# MATRIX-x1.net
KiCad netlist of a schematic drawn in Altium Designer
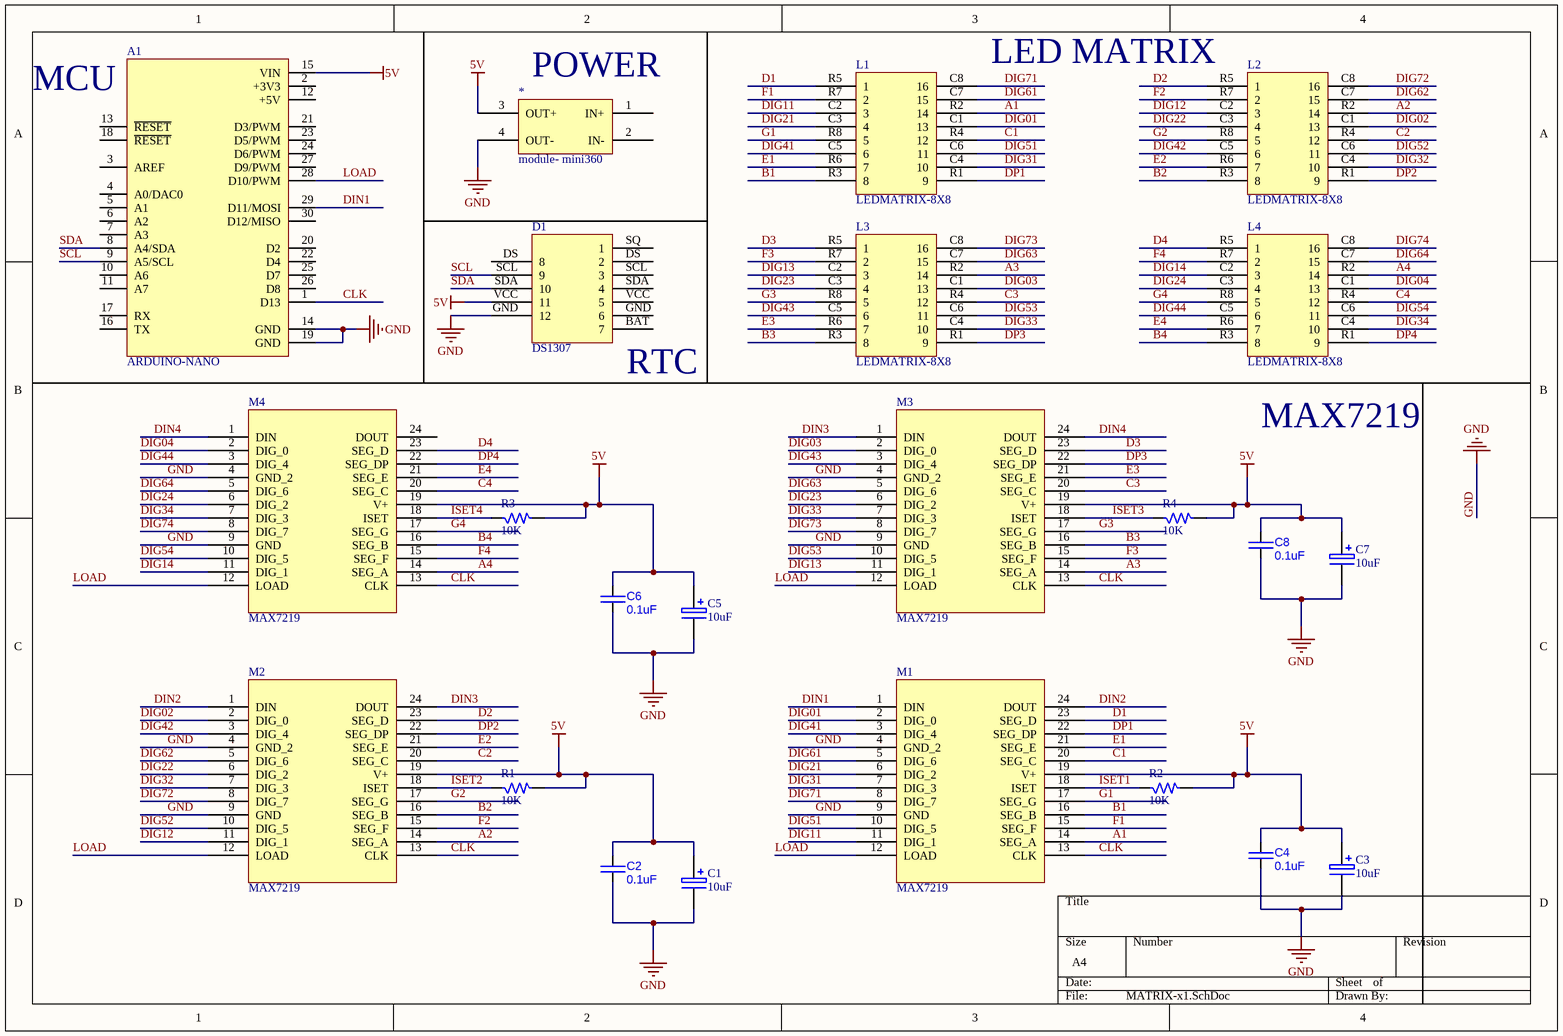
[diagram p0: MATRIX-x1.SchDoc]

(export (version "E")
  (design (tool "Eeschema 10.0.6"))
  (components
    (comp (ref "*")
      (value "module- mini360")
      (footprint "MODULE-MINI360")
      (libsource (lib "KHOEMACH_LIB") (part "module- mini360"))
    )
    (comp (ref "A1")
      (value "ARDUINO-NANO")
      (footprint "ARDUINO-NANO")
      (libsource (lib "KHOEMACH_LIB") (part "ARDUINO-NANO"))
    )
    (comp (ref "C1")
      (value "10uF")
      (footprint "CP1/2")
      (description "Cap")
      (libsource (lib "My library altium") (part "CAP hoa"))
    )
    (comp (ref "C2")
      (value "0.1uF")
      (footprint "CAPC2012X135N")
      (description "Capacitor SMD Cer 1.8nF 10% 50V X7R 0805")
      (fields (field (name "TOLERANCE") "±10%") (field (name "Comment") "approved sub OK"))
      (libsource (lib "My library altium") (part "CAP C_0805"))
    )
    (comp (ref "C3")
      (value "10uF")
      (footprint "CP1/2")
      (description "Cap")
      (libsource (lib "My library altium") (part "CAP hoa"))
    )
    (comp (ref "C4")
      (value "0.1uF")
      (footprint "CAPC2012X135N")
      (description "Capacitor SMD Cer 1.8nF 10% 50V X7R 0805")
      (fields (field (name "TOLERANCE") "±10%") (field (name "Comment") "approved sub OK"))
      (libsource (lib "My library altium") (part "CAP C_0805"))
    )
    (comp (ref "C5")
      (value "10uF")
      (footprint "CP1/2")
      (description "Cap")
      (libsource (lib "My library altium") (part "CAP hoa"))
    )
    (comp (ref "C6")
      (value "0.1uF")
      (footprint "CAPC2012X135N")
      (description "Capacitor SMD Cer 1.8nF 10% 50V X7R 0805")
      (fields (field (name "TOLERANCE") "±10%") (field (name "Comment") "approved sub OK"))
      (libsource (lib "My library altium") (part "CAP C_0805"))
    )
    (comp (ref "C7")
      (value "10uF")
      (footprint "CP1/2")
      (description "Cap")
      (libsource (lib "My library altium") (part "CAP hoa"))
    )
    (comp (ref "C8")
      (value "0.1uF")
      (footprint "CAPC2012X135N")
      (description "Capacitor SMD Cer 1.8nF 10% 50V X7R 0805")
      (fields (field (name "TOLERANCE") "±10%") (field (name "Comment") "approved sub OK"))
      (libsource (lib "My library altium") (part "CAP C_0805"))
    )
    (comp (ref "D1")
      (value "DS1307")
      (footprint "DS1307-MODULE")
      (libsource (lib "KHOEMACH_LIB") (part "DS1307_MODULE"))
    )
    (comp (ref "L1")
      (value "LEDMATRIX-8X8")
      (footprint "LEDMATRIX_8X8")
      (libsource (lib "KHOEMACH_LIB") (part "LEDMATRIX-8X8"))
    )
    (comp (ref "L2")
      (value "LEDMATRIX-8X8")
      (footprint "LEDMATRIX_8X8")
      (libsource (lib "KHOEMACH_LIB") (part "LEDMATRIX-8X8"))
    )
    (comp (ref "L3")
      (value "LEDMATRIX-8X8")
      (footprint "LEDMATRIX_8X8")
      (libsource (lib "KHOEMACH_LIB") (part "LEDMATRIX-8X8"))
    )
    (comp (ref "L4")
      (value "LEDMATRIX-8X8")
      (footprint "LEDMATRIX_8X8")
      (libsource (lib "KHOEMACH_LIB") (part "LEDMATRIX-8X8"))
    )
    (comp (ref "M1")
      (value "MAX7219")
      (footprint "MAX7219")
      (libsource (lib "KHOEMACH_LIB") (part "MAX7219"))
    )
    (comp (ref "M2")
      (value "MAX7219")
      (footprint "MAX7219")
      (libsource (lib "KHOEMACH_LIB") (part "MAX7219"))
    )
    (comp (ref "M3")
      (value "MAX7219")
      (footprint "MAX7219")
      (libsource (lib "KHOEMACH_LIB") (part "MAX7219"))
    )
    (comp (ref "M4")
      (value "MAX7219")
      (footprint "MAX7219")
      (libsource (lib "KHOEMACH_LIB") (part "MAX7219"))
    )
    (comp (ref "R1")
      (value "10K")
      (footprint "SM-RES-1206")
      (description "Resistor 1/4W")
      (libsource (lib "syhaunguyen") (part "R"))
    )
    (comp (ref "R2")
      (value "10K")
      (footprint "SM-RES-1206")
      (description "Resistor 1/4W")
      (libsource (lib "syhaunguyen") (part "R"))
    )
    (comp (ref "R3")
      (value "10K")
      (footprint "SM-RES-1206")
      (description "Resistor 1/4W")
      (libsource (lib "syhaunguyen") (part "R"))
    )
    (comp (ref "R4")
      (value "10K")
      (footprint "SM-RES-1206")
      (description "Resistor 1/4W")
      (libsource (lib "syhaunguyen") (part "R"))
    )
  )
  (nets
    (net (code "1") (name "/A1") (class "Default")
      (node (ref "L1") (pin "R2") (pinfunction "14_R2") (pintype "passive"))
      (node (ref "M1") (pin "14") (pinfunction "SEG_A_14") (pintype "passive"))
    )
    (net (code "2") (name "/A2") (class "Default")
      (node (ref "L2") (pin "R2") (pinfunction "14_R2") (pintype "passive"))
      (node (ref "M2") (pin "14") (pinfunction "SEG_A_14") (pintype "passive"))
    )
    (net (code "3") (name "/A3") (class "Default")
      (node (ref "L3") (pin "R2") (pinfunction "14_R2") (pintype "passive"))
      (node (ref "M3") (pin "14") (pinfunction "SEG_A_14") (pintype "passive"))
    )
    (net (code "4") (name "/A4") (class "Default")
      (node (ref "L4") (pin "R2") (pinfunction "14_R2") (pintype "passive"))
      (node (ref "M4") (pin "14") (pinfunction "SEG_A_14") (pintype "passive"))
    )
    (net (code "5") (name "/B1") (class "Default")
      (node (ref "L1") (pin "R3") (pinfunction "8_R3") (pintype "passive"))
      (node (ref "M1") (pin "16") (pinfunction "SEG_B_16") (pintype "passive"))
    )
    (net (code "6") (name "/B2") (class "Default")
      (node (ref "L2") (pin "R3") (pinfunction "8_R3") (pintype "passive"))
      (node (ref "M2") (pin "16") (pinfunction "SEG_B_16") (pintype "passive"))
    )
    (net (code "7") (name "/B3") (class "Default")
      (node (ref "L3") (pin "R3") (pinfunction "8_R3") (pintype "passive"))
      (node (ref "M3") (pin "16") (pinfunction "SEG_B_16") (pintype "passive"))
    )
    (net (code "8") (name "/B4") (class "Default")
      (node (ref "L4") (pin "R3") (pinfunction "8_R3") (pintype "passive"))
      (node (ref "M4") (pin "16") (pinfunction "SEG_B_16") (pintype "passive"))
    )
    (net (code "9") (name "/C1") (class "Default")
      (node (ref "L1") (pin "R4") (pinfunction "12_R4") (pintype "passive"))
      (node (ref "M1") (pin "20") (pinfunction "SEG_C_20") (pintype "passive"))
    )
    (net (code "10") (name "/C2") (class "Default")
      (node (ref "L2") (pin "R4") (pinfunction "12_R4") (pintype "passive"))
      (node (ref "M2") (pin "20") (pinfunction "SEG_C_20") (pintype "passive"))
    )
    (net (code "11") (name "/C3") (class "Default")
      (node (ref "L3") (pin "R4") (pinfunction "12_R4") (pintype "passive"))
      (node (ref "M3") (pin "20") (pinfunction "SEG_C_20") (pintype "passive"))
    )
    (net (code "12") (name "/C4") (class "Default")
      (node (ref "L4") (pin "R4") (pinfunction "12_R4") (pintype "passive"))
      (node (ref "M4") (pin "20") (pinfunction "SEG_C_20") (pintype "passive"))
    )
    (net (code "13") (name "/CLK") (class "Default")
      (node (ref "A1") (pin "1") (pinfunction "D13_1") (pintype "passive"))
      (node (ref "M1") (pin "13") (pinfunction "CLK_13") (pintype "passive"))
      (node (ref "M2") (pin "13") (pinfunction "CLK_13") (pintype "passive"))
      (node (ref "M3") (pin "13") (pinfunction "CLK_13") (pintype "passive"))
      (node (ref "M4") (pin "13") (pinfunction "CLK_13") (pintype "passive"))
    )
    (net (code "14") (name "/D1") (class "Default")
      (node (ref "L1") (pin "R5") (pinfunction "1_R5") (pintype "passive"))
      (node (ref "M1") (pin "23") (pinfunction "SEG_D_23") (pintype "passive"))
    )
    (net (code "15") (name "/D2") (class "Default")
      (node (ref "L2") (pin "R5") (pinfunction "1_R5") (pintype "passive"))
      (node (ref "M2") (pin "23") (pinfunction "SEG_D_23") (pintype "passive"))
    )
    (net (code "16") (name "/D3") (class "Default")
      (node (ref "L3") (pin "R5") (pinfunction "1_R5") (pintype "passive"))
      (node (ref "M3") (pin "23") (pinfunction "SEG_D_23") (pintype "passive"))
    )
    (net (code "17") (name "/D4") (class "Default")
      (node (ref "L4") (pin "R5") (pinfunction "1_R5") (pintype "passive"))
      (node (ref "M4") (pin "23") (pinfunction "SEG_D_23") (pintype "passive"))
    )
    (net (code "18") (name "/DIG01") (class "Default")
      (node (ref "L1") (pin "C1") (pinfunction "13_C1") (pintype "passive"))
      (node (ref "M1") (pin "2") (pinfunction "DIG_0_2") (pintype "passive"))
    )
    (net (code "19") (name "/DIG02") (class "Default")
      (node (ref "L2") (pin "C1") (pinfunction "13_C1") (pintype "passive"))
      (node (ref "M2") (pin "2") (pinfunction "DIG_0_2") (pintype "passive"))
    )
    (net (code "20") (name "/DIG03") (class "Default")
      (node (ref "L3") (pin "C1") (pinfunction "13_C1") (pintype "passive"))
      (node (ref "M3") (pin "2") (pinfunction "DIG_0_2") (pintype "passive"))
    )
    (net (code "21") (name "/DIG04") (class "Default")
      (node (ref "L4") (pin "C1") (pinfunction "13_C1") (pintype "passive"))
      (node (ref "M4") (pin "2") (pinfunction "DIG_0_2") (pintype "passive"))
    )
    (net (code "22") (name "/DIG11") (class "Default")
      (node (ref "L1") (pin "C2") (pinfunction "3_C2") (pintype "passive"))
      (node (ref "M1") (pin "11") (pinfunction "DIG_1_11") (pintype "passive"))
    )
    (net (code "23") (name "/DIG12") (class "Default")
      (node (ref "L2") (pin "C2") (pinfunction "3_C2") (pintype "passive"))
      (node (ref "M2") (pin "11") (pinfunction "DIG_1_11") (pintype "passive"))
    )
    (net (code "24") (name "/DIG13") (class "Default")
      (node (ref "L3") (pin "C2") (pinfunction "3_C2") (pintype "passive"))
      (node (ref "M3") (pin "11") (pinfunction "DIG_1_11") (pintype "passive"))
    )
    (net (code "25") (name "/DIG14") (class "Default")
      (node (ref "L4") (pin "C2") (pinfunction "3_C2") (pintype "passive"))
      (node (ref "M4") (pin "11") (pinfunction "DIG_1_11") (pintype "passive"))
    )
    (net (code "26") (name "/DIG21") (class "Default")
      (node (ref "L1") (pin "C3") (pinfunction "4_C3") (pintype "passive"))
      (node (ref "M1") (pin "6") (pinfunction "DIG_2_6") (pintype "passive"))
    )
    (net (code "27") (name "/DIG22") (class "Default")
      (node (ref "L2") (pin "C3") (pinfunction "4_C3") (pintype "passive"))
      (node (ref "M2") (pin "6") (pinfunction "DIG_2_6") (pintype "passive"))
    )
    (net (code "28") (name "/DIG23") (class "Default")
      (node (ref "L3") (pin "C3") (pinfunction "4_C3") (pintype "passive"))
      (node (ref "M3") (pin "6") (pinfunction "DIG_2_6") (pintype "passive"))
    )
    (net (code "29") (name "/DIG24") (class "Default")
      (node (ref "L4") (pin "C3") (pinfunction "4_C3") (pintype "passive"))
      (node (ref "M4") (pin "6") (pinfunction "DIG_2_6") (pintype "passive"))
    )
    (net (code "30") (name "/DIG31") (class "Default")
      (node (ref "L1") (pin "C4") (pinfunction "10_C4") (pintype "passive"))
      (node (ref "M1") (pin "7") (pinfunction "DIG_3_7") (pintype "passive"))
    )
    (net (code "31") (name "/DIG32") (class "Default")
      (node (ref "L2") (pin "C4") (pinfunction "10_C4") (pintype "passive"))
      (node (ref "M2") (pin "7") (pinfunction "DIG_3_7") (pintype "passive"))
    )
    (net (code "32") (name "/DIG33") (class "Default")
      (node (ref "L3") (pin "C4") (pinfunction "10_C4") (pintype "passive"))
      (node (ref "M3") (pin "7") (pinfunction "DIG_3_7") (pintype "passive"))
    )
    (net (code "33") (name "/DIG34") (class "Default")
      (node (ref "L4") (pin "C4") (pinfunction "10_C4") (pintype "passive"))
      (node (ref "M4") (pin "7") (pinfunction "DIG_3_7") (pintype "passive"))
    )
    (net (code "34") (name "/DIG41") (class "Default")
      (node (ref "L1") (pin "C5") (pinfunction "6_C5") (pintype "passive"))
      (node (ref "M1") (pin "3") (pinfunction "DIG_4_3") (pintype "passive"))
    )
    (net (code "35") (name "/DIG42") (class "Default")
      (node (ref "L2") (pin "C5") (pinfunction "6_C5") (pintype "passive"))
      (node (ref "M2") (pin "3") (pinfunction "DIG_4_3") (pintype "passive"))
    )
    (net (code "36") (name "/DIG43") (class "Default")
      (node (ref "L3") (pin "C5") (pinfunction "6_C5") (pintype "passive"))
      (node (ref "M3") (pin "3") (pinfunction "DIG_4_3") (pintype "passive"))
    )
    (net (code "37") (name "/DIG44") (class "Default")
      (node (ref "L4") (pin "C5") (pinfunction "6_C5") (pintype "passive"))
      (node (ref "M4") (pin "3") (pinfunction "DIG_4_3") (pintype "passive"))
    )
    (net (code "38") (name "/DIG51") (class "Default")
      (node (ref "L1") (pin "C6") (pinfunction "11_C6") (pintype "passive"))
      (node (ref "M1") (pin "10") (pinfunction "DIG_5_10") (pintype "passive"))
    )
    (net (code "39") (name "/DIG52") (class "Default")
      (node (ref "L2") (pin "C6") (pinfunction "11_C6") (pintype "passive"))
      (node (ref "M2") (pin "10") (pinfunction "DIG_5_10") (pintype "passive"))
    )
    (net (code "40") (name "/DIG53") (class "Default")
      (node (ref "L3") (pin "C6") (pinfunction "11_C6") (pintype "passive"))
      (node (ref "M3") (pin "10") (pinfunction "DIG_5_10") (pintype "passive"))
    )
    (net (code "41") (name "/DIG54") (class "Default")
      (node (ref "L4") (pin "C6") (pinfunction "11_C6") (pintype "passive"))
      (node (ref "M4") (pin "10") (pinfunction "DIG_5_10") (pintype "passive"))
    )
    (net (code "42") (name "/DIG61") (class "Default")
      (node (ref "L1") (pin "C7") (pinfunction "15_C7") (pintype "passive"))
      (node (ref "M1") (pin "5") (pinfunction "DIG_6_5") (pintype "passive"))
    )
    (net (code "43") (name "/DIG62") (class "Default")
      (node (ref "L2") (pin "C7") (pinfunction "15_C7") (pintype "passive"))
      (node (ref "M2") (pin "5") (pinfunction "DIG_6_5") (pintype "passive"))
    )
    (net (code "44") (name "/DIG63") (class "Default")
      (node (ref "L3") (pin "C7") (pinfunction "15_C7") (pintype "passive"))
      (node (ref "M3") (pin "5") (pinfunction "DIG_6_5") (pintype "passive"))
    )
    (net (code "45") (name "/DIG64") (class "Default")
      (node (ref "L4") (pin "C7") (pinfunction "15_C7") (pintype "passive"))
      (node (ref "M4") (pin "5") (pinfunction "DIG_6_5") (pintype "passive"))
    )
    (net (code "46") (name "/DIG71") (class "Default")
      (node (ref "L1") (pin "C8") (pinfunction "16_C8") (pintype "passive"))
      (node (ref "M1") (pin "8") (pinfunction "DIG_7_8") (pintype "passive"))
    )
    (net (code "47") (name "/DIG72") (class "Default")
      (node (ref "L2") (pin "C8") (pinfunction "16_C8") (pintype "passive"))
      (node (ref "M2") (pin "8") (pinfunction "DIG_7_8") (pintype "passive"))
    )
    (net (code "48") (name "/DIG73") (class "Default")
      (node (ref "L3") (pin "C8") (pinfunction "16_C8") (pintype "passive"))
      (node (ref "M3") (pin "8") (pinfunction "DIG_7_8") (pintype "passive"))
    )
    (net (code "49") (name "/DIG74") (class "Default")
      (node (ref "L4") (pin "C8") (pinfunction "16_C8") (pintype "passive"))
      (node (ref "M4") (pin "8") (pinfunction "DIG_7_8") (pintype "passive"))
    )
    (net (code "50") (name "/DIN1") (class "Default")
      (node (ref "A1") (pin "29") (pinfunction "D11/MOSI_29") (pintype "passive"))
      (node (ref "M1") (pin "1") (pinfunction "DIN_1") (pintype "passive"))
    )
    (net (code "51") (name "/DIN2") (class "Default")
      (node (ref "M1") (pin "24") (pinfunction "DOUT_24") (pintype "passive"))
      (node (ref "M2") (pin "1") (pinfunction "DIN_1") (pintype "passive"))
    )
    (net (code "52") (name "/DIN3") (class "Default")
      (node (ref "M2") (pin "24") (pinfunction "DOUT_24") (pintype "passive"))
      (node (ref "M3") (pin "1") (pinfunction "DIN_1") (pintype "passive"))
    )
    (net (code "53") (name "/DIN4") (class "Default")
      (node (ref "M3") (pin "24") (pinfunction "DOUT_24") (pintype "passive"))
      (node (ref "M4") (pin "1") (pinfunction "DIN_1") (pintype "passive"))
    )
    (net (code "54") (name "/DP1") (class "Default")
      (node (ref "L1") (pin "R1") (pinfunction "9_R1") (pintype "passive"))
      (node (ref "M1") (pin "22") (pinfunction "SEG_DP_22") (pintype "passive"))
    )
    (net (code "55") (name "/DP2") (class "Default")
      (node (ref "L2") (pin "R1") (pinfunction "9_R1") (pintype "passive"))
      (node (ref "M2") (pin "22") (pinfunction "SEG_DP_22") (pintype "passive"))
    )
    (net (code "56") (name "/DP3") (class "Default")
      (node (ref "L3") (pin "R1") (pinfunction "9_R1") (pintype "passive"))
      (node (ref "M3") (pin "22") (pinfunction "SEG_DP_22") (pintype "passive"))
    )
    (net (code "57") (name "/DP4") (class "Default")
      (node (ref "L4") (pin "R1") (pinfunction "9_R1") (pintype "passive"))
      (node (ref "M4") (pin "22") (pinfunction "SEG_DP_22") (pintype "passive"))
    )
    (net (code "58") (name "/E1") (class "Default")
      (node (ref "L1") (pin "R6") (pinfunction "7_R6") (pintype "passive"))
      (node (ref "M1") (pin "21") (pinfunction "SEG_E_21") (pintype "passive"))
    )
    (net (code "59") (name "/E2") (class "Default")
      (node (ref "L2") (pin "R6") (pinfunction "7_R6") (pintype "passive"))
      (node (ref "M2") (pin "21") (pinfunction "SEG_E_21") (pintype "passive"))
    )
    (net (code "60") (name "/E3") (class "Default")
      (node (ref "L3") (pin "R6") (pinfunction "7_R6") (pintype "passive"))
      (node (ref "M3") (pin "21") (pinfunction "SEG_E_21") (pintype "passive"))
    )
    (net (code "61") (name "/E4") (class "Default")
      (node (ref "L4") (pin "R6") (pinfunction "7_R6") (pintype "passive"))
      (node (ref "M4") (pin "21") (pinfunction "SEG_E_21") (pintype "passive"))
    )
    (net (code "62") (name "/F1") (class "Default")
      (node (ref "L1") (pin "R7") (pinfunction "2_R7") (pintype "passive"))
      (node (ref "M1") (pin "15") (pinfunction "SEG_F_15") (pintype "passive"))
    )
    (net (code "63") (name "/F2") (class "Default")
      (node (ref "L2") (pin "R7") (pinfunction "2_R7") (pintype "passive"))
      (node (ref "M2") (pin "15") (pinfunction "SEG_F_15") (pintype "passive"))
    )
    (net (code "64") (name "/F3") (class "Default")
      (node (ref "L3") (pin "R7") (pinfunction "2_R7") (pintype "passive"))
      (node (ref "M3") (pin "15") (pinfunction "SEG_F_15") (pintype "passive"))
    )
    (net (code "65") (name "/F4") (class "Default")
      (node (ref "L4") (pin "R7") (pinfunction "2_R7") (pintype "passive"))
      (node (ref "M4") (pin "15") (pinfunction "SEG_F_15") (pintype "passive"))
    )
    (net (code "66") (name "/G1") (class "Default")
      (node (ref "L1") (pin "R8") (pinfunction "5_R8") (pintype "passive"))
      (node (ref "M1") (pin "17") (pinfunction "SEG_G_17") (pintype "passive"))
    )
    (net (code "67") (name "/G2") (class "Default")
      (node (ref "L2") (pin "R8") (pinfunction "5_R8") (pintype "passive"))
      (node (ref "M2") (pin "17") (pinfunction "SEG_G_17") (pintype "passive"))
    )
    (net (code "68") (name "/G3") (class "Default")
      (node (ref "L3") (pin "R8") (pinfunction "5_R8") (pintype "passive"))
      (node (ref "M3") (pin "17") (pinfunction "SEG_G_17") (pintype "passive"))
    )
    (net (code "69") (name "/G4") (class "Default")
      (node (ref "L4") (pin "R8") (pinfunction "5_R8") (pintype "passive"))
      (node (ref "M4") (pin "17") (pinfunction "SEG_G_17") (pintype "passive"))
    )
    (net (code "70") (name "/ISET1") (class "Default")
      (node (ref "M1") (pin "18") (pinfunction "ISET_18") (pintype "passive"))
      (node (ref "R2") (pin "1") (pinfunction "1_1") (pintype "passive"))
    )
    (net (code "71") (name "/ISET2") (class "Default")
      (node (ref "M2") (pin "18") (pinfunction "ISET_18") (pintype "passive"))
      (node (ref "R1") (pin "1") (pinfunction "1_1") (pintype "passive"))
    )
    (net (code "72") (name "/ISET3") (class "Default")
      (node (ref "M3") (pin "18") (pinfunction "ISET_18") (pintype "passive"))
      (node (ref "R4") (pin "1") (pinfunction "1_1") (pintype "passive"))
    )
    (net (code "73") (name "/ISET4") (class "Default")
      (node (ref "M4") (pin "18") (pinfunction "ISET_18") (pintype "passive"))
      (node (ref "R3") (pin "1") (pinfunction "1_1") (pintype "passive"))
    )
    (net (code "74") (name "/LOAD") (class "Default")
      (node (ref "A1") (pin "28") (pinfunction "D10/PWM_28") (pintype "passive"))
      (node (ref "M1") (pin "12") (pinfunction "LOAD_12") (pintype "passive"))
      (node (ref "M2") (pin "12") (pinfunction "LOAD_12") (pintype "passive"))
      (node (ref "M3") (pin "12") (pinfunction "LOAD_12") (pintype "passive"))
      (node (ref "M4") (pin "12") (pinfunction "LOAD_12") (pintype "passive"))
    )
    (net (code "75") (name "/SCL") (class "Default")
      (node (ref "A1") (pin "9") (pinfunction "A5/SCL_9") (pintype "passive"))
      (node (ref "D1") (pin "SCL") (pinfunction "9_SCL") (pintype "passive"))
    )
    (net (code "76") (name "/SDA") (class "Default")
      (node (ref "A1") (pin "8") (pinfunction "A4/SDA_8") (pintype "passive"))
      (node (ref "D1") (pin "SDA") (pinfunction "10_SDA") (pintype "passive"))
    )
    (net (code "77") (name "5V") (class "Default")
      (node (ref "*") (pin "3") (pinfunction "OUT+_3") (pintype "passive"))
      (node (ref "A1") (pin "15") (pinfunction "VIN_15") (pintype "passive"))
      (node (ref "C1") (pin "1") (pintype "passive"))
      (node (ref "C2") (pin "1") (pintype "passive"))
      (node (ref "C3") (pin "1") (pintype "passive"))
      (node (ref "C4") (pin "1") (pintype "passive"))
      (node (ref "C5") (pin "1") (pintype "passive"))
      (node (ref "C6") (pin "1") (pintype "passive"))
      (node (ref "C7") (pin "1") (pintype "passive"))
      (node (ref "C8") (pin "1") (pintype "passive"))
      (node (ref "D1") (pin "VCC") (pinfunction "11_VCC") (pintype "passive"))
      (node (ref "M1") (pin "19") (pinfunction "V+_19") (pintype "power_in"))
      (node (ref "M2") (pin "19") (pinfunction "V+_19") (pintype "power_in"))
      (node (ref "M3") (pin "19") (pinfunction "V+_19") (pintype "power_in"))
      (node (ref "M4") (pin "19") (pinfunction "V+_19") (pintype "power_in"))
      (node (ref "R1") (pin "2") (pinfunction "2_2") (pintype "passive"))
      (node (ref "R2") (pin "2") (pinfunction "2_2") (pintype "passive"))
      (node (ref "R3") (pin "2") (pinfunction "2_2") (pintype "passive"))
      (node (ref "R4") (pin "2") (pinfunction "2_2") (pintype "passive"))
    )
    (net (code "78") (name "GND") (class "Default")
      (node (ref "*") (pin "4") (pinfunction "OUT-_4") (pintype "passive"))
      (node (ref "A1") (pin "14") (pinfunction "GND_14") (pintype "passive"))
      (node (ref "A1") (pin "19") (pinfunction "GND_19") (pintype "passive"))
      (node (ref "C1") (pin "2") (pintype "passive"))
      (node (ref "C2") (pin "2") (pintype "passive"))
      (node (ref "C3") (pin "2") (pintype "passive"))
      (node (ref "C4") (pin "2") (pintype "passive"))
      (node (ref "C5") (pin "2") (pintype "passive"))
      (node (ref "C6") (pin "2") (pintype "passive"))
      (node (ref "C7") (pin "2") (pintype "passive"))
      (node (ref "C8") (pin "2") (pintype "passive"))
      (node (ref "D1") (pin "GND") (pinfunction "12_GND") (pintype "passive"))
      (node (ref "M1") (pin "4") (pinfunction "GND_2_4") (pintype "power_in"))
      (node (ref "M1") (pin "9") (pinfunction "GND_9") (pintype "power_in"))
      (node (ref "M2") (pin "4") (pinfunction "GND_2_4") (pintype "power_in"))
      (node (ref "M2") (pin "9") (pinfunction "GND_9") (pintype "power_in"))
      (node (ref "M3") (pin "4") (pinfunction "GND_2_4") (pintype "power_in"))
      (node (ref "M3") (pin "9") (pinfunction "GND_9") (pintype "power_in"))
      (node (ref "M4") (pin "4") (pinfunction "GND_2_4") (pintype "power_in"))
      (node (ref "M4") (pin "9") (pinfunction "GND_9") (pintype "power_in"))
    )
    (net (code "79") (name "unconnected-(*-IN+-Pad1)") (class "Default")
      (node (ref "*") (pin "1") (pinfunction "IN+_1") (pintype "passive"))
    )
    (net (code "80") (name "unconnected-(*-IN--Pad2)") (class "Default")
      (node (ref "*") (pin "2") (pinfunction "IN-_2") (pintype "passive"))
    )
    (net (code "81") (name "unconnected-(A1-+3V3-Pad2)") (class "Default")
      (node (ref "A1") (pin "2") (pinfunction "+3V3_2") (pintype "passive"))
    )
    (net (code "82") (name "unconnected-(A1-+5V-Pad12)") (class "Default")
      (node (ref "A1") (pin "12") (pinfunction "+5V_12") (pintype "passive"))
    )
    (net (code "83") (name "unconnected-(A1-A0{slash}DAC0-Pad4)") (class "Default")
      (node (ref "A1") (pin "4") (pinfunction "A0/DAC0_4") (pintype "passive"))
    )
    (net (code "84") (name "unconnected-(A1-A1-Pad5)") (class "Default")
      (node (ref "A1") (pin "5") (pinfunction "A1_5") (pintype "passive"))
    )
    (net (code "85") (name "unconnected-(A1-A2-Pad6)") (class "Default")
      (node (ref "A1") (pin "6") (pinfunction "A2_6") (pintype "passive"))
    )
    (net (code "86") (name "unconnected-(A1-A3-Pad7)") (class "Default")
      (node (ref "A1") (pin "7") (pinfunction "A3_7") (pintype "passive"))
    )
    (net (code "87") (name "unconnected-(A1-A6-Pad10)") (class "Default")
      (node (ref "A1") (pin "10") (pinfunction "A6_10") (pintype "passive"))
    )
    (net (code "88") (name "unconnected-(A1-A7-Pad11)") (class "Default")
      (node (ref "A1") (pin "11") (pinfunction "A7_11") (pintype "passive"))
    )
    (net (code "89") (name "unconnected-(A1-AREF-Pad3)") (class "Default")
      (node (ref "A1") (pin "3") (pinfunction "AREF_3") (pintype "passive"))
    )
    (net (code "90") (name "unconnected-(A1-D2-Pad20)") (class "Default")
      (node (ref "A1") (pin "20") (pinfunction "D2_20") (pintype "passive"))
    )
    (net (code "91") (name "unconnected-(A1-D3{slash}PWM-Pad21)") (class "Default")
      (node (ref "A1") (pin "21") (pinfunction "D3/PWM_21") (pintype "passive"))
    )
    (net (code "92") (name "unconnected-(A1-D4-Pad22)") (class "Default")
      (node (ref "A1") (pin "22") (pinfunction "D4_22") (pintype "passive"))
    )
    (net (code "93") (name "unconnected-(A1-D5{slash}PWM-Pad23)") (class "Default")
      (node (ref "A1") (pin "23") (pinfunction "D5/PWM_23") (pintype "passive"))
    )
    (net (code "94") (name "unconnected-(A1-D6{slash}PWM-Pad24)") (class "Default")
      (node (ref "A1") (pin "24") (pinfunction "D6/PWM_24") (pintype "passive"))
    )
    (net (code "95") (name "unconnected-(A1-D7-Pad25)") (class "Default")
      (node (ref "A1") (pin "25") (pinfunction "D7_25") (pintype "passive"))
    )
    (net (code "96") (name "unconnected-(A1-D8-Pad26)") (class "Default")
      (node (ref "A1") (pin "26") (pinfunction "D8_26") (pintype "passive"))
    )
    (net (code "97") (name "unconnected-(A1-D9{slash}PWM-Pad27)") (class "Default")
      (node (ref "A1") (pin "27") (pinfunction "D9/PWM_27") (pintype "passive"))
    )
    (net (code "98") (name "unconnected-(A1-D12{slash}MISO-Pad30)") (class "Default")
      (node (ref "A1") (pin "30") (pinfunction "D12/MISO_30") (pintype "passive"))
    )
    (net (code "99") (name "unconnected-(A1-RX-Pad17)") (class "Default")
      (node (ref "A1") (pin "17") (pinfunction "RX_17") (pintype "passive"))
    )
    (net (code "100") (name "unconnected-(A1-TX-Pad16)") (class "Default")
      (node (ref "A1") (pin "16") (pinfunction "TX_16") (pintype "passive"))
    )
    (net (code "101") (name "unconnected-(A1-~{RESET}-Pad13)") (class "Default")
      (node (ref "A1") (pin "13") (pinfunction "~{RESET}_13") (pintype "passive"))
    )
    (net (code "102") (name "unconnected-(A1-~{RESET}-Pad18)") (class "Default")
      (node (ref "A1") (pin "18") (pinfunction "~{RESET}_18") (pintype "passive"))
    )
    (net (code "103") (name "unconnected-(D1-1-PadSQ)") (class "Default")
      (node (ref "D1") (pin "SQ") (pinfunction "1_SQ") (pintype "passive"))
    )
    (net (code "104") (name "unconnected-(D1-2-PadDS)") (class "Default")
      (node (ref "D1") (pin "DS") (pinfunction "2_DS") (pintype "passive"))
    )
    (net (code "105") (name "unconnected-(D1-3-PadSCL)") (class "Default")
      (node (ref "D1") (pin "SCL") (pinfunction "3_SCL") (pintype "passive"))
    )
    (net (code "106") (name "unconnected-(D1-4-PadSDA)") (class "Default")
      (node (ref "D1") (pin "SDA") (pinfunction "4_SDA") (pintype "passive"))
    )
    (net (code "107") (name "unconnected-(D1-5-PadVCC)") (class "Default")
      (node (ref "D1") (pin "VCC") (pinfunction "5_VCC") (pintype "passive"))
    )
    (net (code "108") (name "unconnected-(D1-6-PadGND)") (class "Default")
      (node (ref "D1") (pin "GND") (pinfunction "6_GND") (pintype "passive"))
    )
    (net (code "109") (name "unconnected-(D1-7-PadBAT)") (class "Default")
      (node (ref "D1") (pin "BAT") (pinfunction "7_BAT") (pintype "passive"))
    )
    (net (code "110") (name "unconnected-(D1-8-PadDS)") (class "Default")
      (node (ref "D1") (pin "DS") (pinfunction "8_DS") (pintype "passive"))
    )
    (net (code "111") (name "unconnected-(M4-DOUT-Pad24)") (class "Default")
      (node (ref "M4") (pin "24") (pinfunction "DOUT_24") (pintype "passive"))
    )
  )
)
